# basic-dual-supply.net
KiCad netlist of a schematic drawn in EAGLE
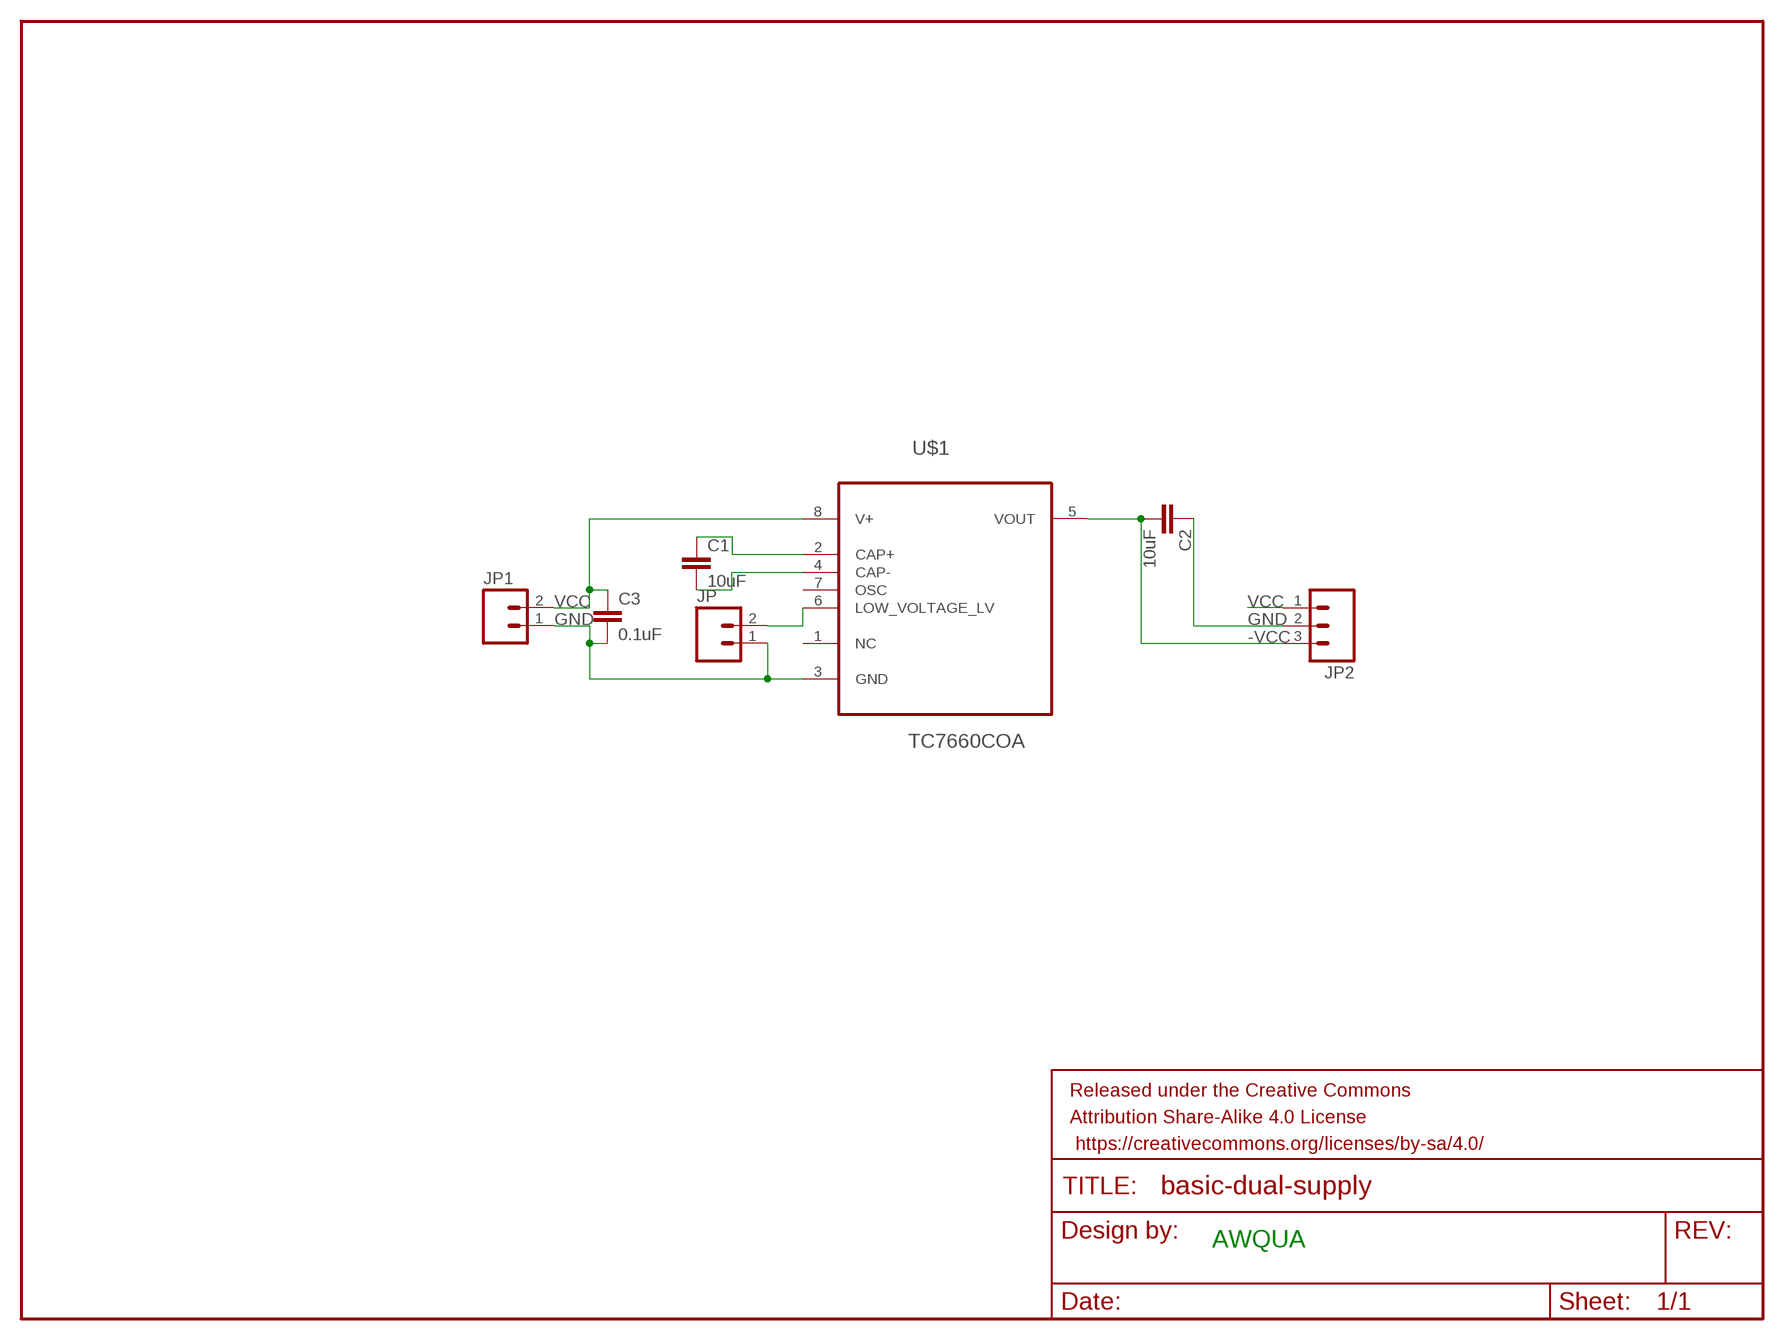
[diagram p0: schematic, sheet 1]

(export (version "E")
  (design (tool "Eeschema 10.0.6"))
  (components
    (comp (ref "C1")
      (value "10uF")
      (footprint "eagle-import:0603-CAP")
      (libsource (lib "eagle-import") (part "CAP0603-CAP"))
    )
    (comp (ref "C2")
      (value "10uF")
      (footprint "eagle-import:0603-CAP")
      (libsource (lib "eagle-import") (part "CAP0603-CAP"))
    )
    (comp (ref "C3")
      (value "0.1uF")
      (footprint "eagle-import:0603-CAP")
      (libsource (lib "eagle-import") (part "CAP0603-CAP"))
    )
    (comp (ref "FRAME1")
      (value "FRAME-LETTER")
      (footprint "eagle-import:CREATIVE_COMMONS")
      (libsource (lib "eagle-import") (part "FRAME-LETTER"))
    )
    (comp (ref "JP")
      (value "M02PTH")
      (footprint "eagle-import:1X02")
      (libsource (lib "eagle-import") (part "M02PTH"))
    )
    (comp (ref "JP1")
      (value "M02PTH")
      (footprint "eagle-import:1X02")
      (libsource (lib "eagle-import") (part "M02PTH"))
    )
    (comp (ref "JP2")
      (value "M03PTH")
      (footprint "eagle-import:1X03")
      (libsource (lib "eagle-import") (part "M03PTH"))
    )
    (comp (ref "U$1")
      (value "TC7660COA")
      (footprint "eagle-import:SOIC127P600X175-8N")
      (fields (field (name "MF") "Microchip"))
      (libsource (lib "eagle-import") (part "TC7660COA"))
    )
  )
  (nets
    (net (code "1") (name "/-VCC") (class "Default")
      (node (ref "C2") (pin "2") (pinfunction "2_2") (pintype "passive"))
      (node (ref "JP2") (pin "3") (pinfunction "3_3") (pintype "passive"))
      (node (ref "U$1") (pin "5") (pinfunction "VOUT_5") (pintype "output"))
    )
    (net (code "2") (name "/GND") (class "Default")
      (node (ref "C2") (pin "1") (pinfunction "1_1") (pintype "passive"))
      (node (ref "C3") (pin "2") (pinfunction "2_2") (pintype "passive"))
      (node (ref "JP") (pin "1") (pinfunction "1_1") (pintype "passive"))
      (node (ref "JP1") (pin "1") (pinfunction "1_1") (pintype "passive"))
      (node (ref "JP2") (pin "2") (pinfunction "2_2") (pintype "passive"))
      (node (ref "U$1") (pin "3") (pinfunction "GND_3") (pintype "passive"))
    )
    (net (code "3") (name "/VCC") (class "Default")
      (node (ref "C3") (pin "1") (pinfunction "1_1") (pintype "passive"))
      (node (ref "JP1") (pin "2") (pinfunction "2_2") (pintype "passive"))
      (node (ref "JP2") (pin "1") (pinfunction "1_1") (pintype "passive"))
      (node (ref "U$1") (pin "8") (pinfunction "V+_8") (pintype "power_in"))
    )
    (net (code "4") (name "Net-(U$1-CAP+)") (class "Default")
      (node (ref "C1") (pin "1") (pinfunction "1_1") (pintype "passive"))
      (node (ref "U$1") (pin "2") (pinfunction "CAP+_2") (pintype "passive"))
    )
    (net (code "5") (name "Net-(U$1-CAP-)") (class "Default")
      (node (ref "C1") (pin "2") (pinfunction "2_2") (pintype "passive"))
      (node (ref "U$1") (pin "4") (pinfunction "CAP-_4") (pintype "passive"))
    )
    (net (code "6") (name "Net-(U$1-LOW_VOLTAGE_LV)") (class "Default")
      (node (ref "JP") (pin "2") (pinfunction "2_2") (pintype "passive"))
      (node (ref "U$1") (pin "6") (pinfunction "LOW_VOLTAGE_LV_6") (pintype "power_in"))
    )
    (net (code "7") (name "unconnected-(U$1-NC-Pad1)") (class "Default")
      (node (ref "U$1") (pin "1") (pinfunction "NC_1") (pintype "no_connect"))
    )
    (net (code "8") (name "unconnected-(U$1-OSC-Pad7)") (class "Default")
      (node (ref "U$1") (pin "7") (pinfunction "OSC_7") (pintype "input"))
    )
  )
)
